# STM32-PROX_6.net
KiCad netlist of a schematic drawn in Altium Designer
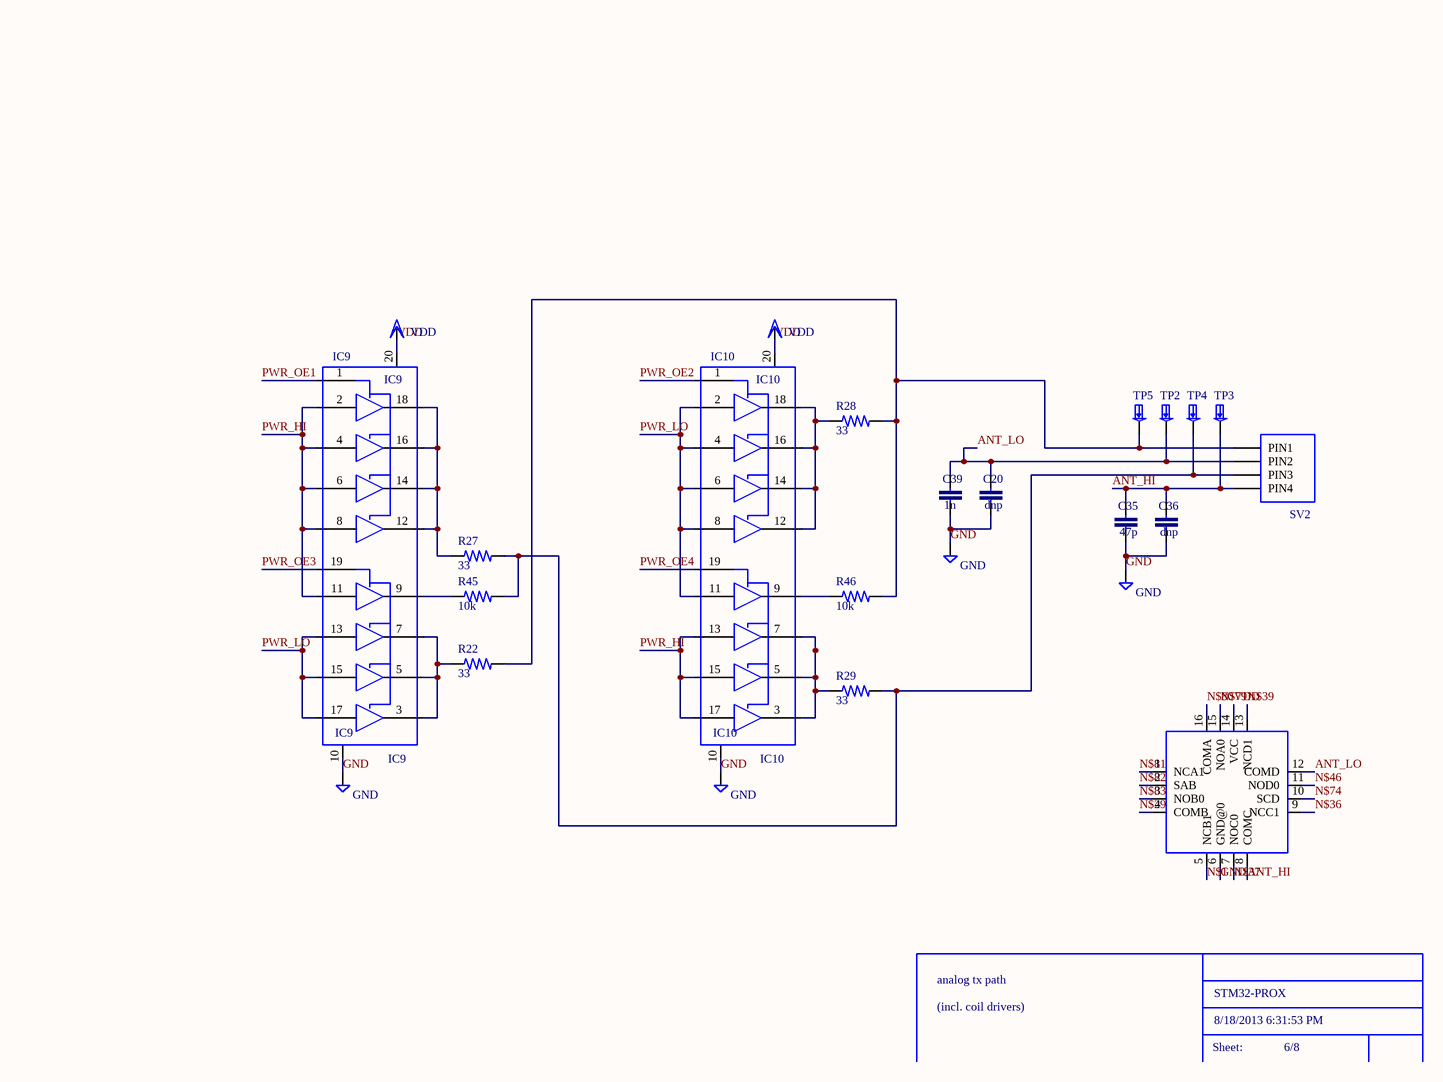
[diagram p0: STM32-PROX_6.SchDoc]

(export (version "E")
  (design (tool "Eeschema 10.0.6"))
  (components
    (comp (ref "C20")
      (value "dnp")
      (footprint "RLC_0603")
      (libsource (lib "STM32-PROX") (part "CAPACITORRLC_0603"))
    )
    (comp (ref "C35")
      (value "47p")
      (footprint "RLC_0603")
      (libsource (lib "STM32-PROX") (part "CAPACITORRLC_0603"))
    )
    (comp (ref "C36")
      (value "dnp")
      (footprint "RLC_0603")
      (libsource (lib "STM32-PROX") (part "CAPACITORRLC_0603"))
    )
    (comp (ref "C39")
      (value "1n")
      (footprint "RLC_0603")
      (libsource (lib "STM32-PROX") (part "CAPACITORRLC_0603"))
    )
    (comp (ref "FRAME5") (value "~") (libsource (lib "STM32-PROX") (part "A4L-LOC")))
    (comp (ref "IC9")
      (value "~")
      (footprint "TSSOP-20")
      (libsource (lib "STM32-PROX") (part "74XX244-OCTAL-TRISTATE-BUFFERS"))
    )
    (comp (ref "IC10")
      (value "~")
      (footprint "TSSOP-20")
      (libsource (lib "STM32-PROX") (part "74XX244-OCTAL-TRISTATE-BUFFERS"))
    )
    (comp (ref "IC12") (value "~") (footprint "QFN16") (libsource (lib "STM32-PROX") (part "NLAST44599")))
    (comp (ref "R22")
      (value "33")
      (footprint "RLC_0603")
      (libsource (lib "STM32-PROX") (part "RESISTORRLC_0603"))
    )
    (comp (ref "R27")
      (value "33")
      (footprint "RLC_0603")
      (libsource (lib "STM32-PROX") (part "RESISTORRLC_0603"))
    )
    (comp (ref "R28")
      (value "33")
      (footprint "RLC_0603")
      (libsource (lib "STM32-PROX") (part "RESISTORRLC_0603"))
    )
    (comp (ref "R29")
      (value "33")
      (footprint "RLC_0603")
      (libsource (lib "STM32-PROX") (part "RESISTORRLC_0603"))
    )
    (comp (ref "R45")
      (value "10k")
      (footprint "RLC_0603")
      (libsource (lib "STM32-PROX") (part "RESISTORRLC_0603"))
    )
    (comp (ref "R46")
      (value "10k")
      (footprint "RLC_0603")
      (libsource (lib "STM32-PROX") (part "RESISTORRLC_0603"))
    )
    (comp (ref "SV2")
      (value "~")
      (footprint "HIROSE-MQ172-4POS")
      (libsource (lib "STM32-PROX") (part "HIROSE-MQ172-4POS"))
    )
    (comp (ref "TP2")
      (value "~")
      (footprint "KEYSTONE-SMD-TESTPOINT-5015")
      (libsource (lib "STM32-PROX") (part "TESTPADKEYSTONE-SMD"))
    )
    (comp (ref "TP3")
      (value "~")
      (footprint "KEYSTONE-SMD-TESTPOINT-5015")
      (libsource (lib "STM32-PROX") (part "TESTPADKEYSTONE-SMD"))
    )
    (comp (ref "TP4")
      (value "~")
      (footprint "KEYSTONE-SMD-TESTPOINT-5015")
      (libsource (lib "STM32-PROX") (part "TESTPADKEYSTONE-SMD"))
    )
    (comp (ref "TP5")
      (value "~")
      (footprint "KEYSTONE-SMD-TESTPOINT-5015")
      (libsource (lib "STM32-PROX") (part "TESTPADKEYSTONE-SMD"))
    )
    (comp (ref "V26") (value "GND") (libsource (lib "STM32-PROX") (part "GND")))
    (comp (ref "V27") (value "GND") (libsource (lib "STM32-PROX") (part "GND")))
    (comp (ref "V41") (value "GND") (libsource (lib "STM32-PROX") (part "GND")))
    (comp (ref "V47") (value "GND") (libsource (lib "STM32-PROX") (part "GND")))
    (comp (ref "VDD5") (value "VDD") (libsource (lib "STM32-PROX") (part "VDD")))
    (comp (ref "VDD6") (value "VDD") (libsource (lib "STM32-PROX") (part "VDD")))
  )
  (nets
    (net (code "1") (name "/ANT_HI") (class "Default")
      (node (ref "C35") (pin "1") (pinfunction "1_1") (pintype "passive"))
      (node (ref "C36") (pin "1") (pinfunction "1_1") (pintype "passive"))
      (node (ref "IC12") (pin "8") (pinfunction "COMC_8") (pintype "passive"))
      (node (ref "SV2") (pin "4") (pinfunction "PIN4_4") (pintype "passive"))
      (node (ref "TP3") (pin "1") (pinfunction "P$1_1") (pintype "passive"))
    )
    (net (code "2") (name "/ANT_LO") (class "Default")
      (node (ref "C20") (pin "1") (pinfunction "1_1") (pintype "passive"))
      (node (ref "C39") (pin "1") (pinfunction "1_1") (pintype "passive"))
      (node (ref "IC12") (pin "12") (pinfunction "COMD_12") (pintype "passive"))
      (node (ref "SV2") (pin "2") (pinfunction "PIN2_2") (pintype "passive"))
      (node (ref "TP2") (pin "1") (pinfunction "P$1_1") (pintype "passive"))
    )
    (net (code "3") (name "/GND") (class "Default")
      (node (ref "C20") (pin "2") (pinfunction "2_2") (pintype "passive"))
      (node (ref "C35") (pin "2") (pinfunction "2_2") (pintype "passive"))
      (node (ref "C36") (pin "2") (pinfunction "2_2") (pintype "passive"))
      (node (ref "C39") (pin "2") (pinfunction "2_2") (pintype "passive"))
      (node (ref "IC10") (pin "10") (pinfunction "VSS_10") (pintype "passive"))
      (node (ref "IC12") (pin "6") (pinfunction "GND@0_6") (pintype "passive"))
      (node (ref "IC9") (pin "10") (pinfunction "VSS_10") (pintype "passive"))
      (node (ref "V26") (pin "0") (pinfunction "GND_0") (pintype "passive"))
      (node (ref "V27") (pin "0") (pinfunction "GND_0") (pintype "passive"))
      (node (ref "V41") (pin "0") (pinfunction "GND_0") (pintype "passive"))
      (node (ref "V47") (pin "0") (pinfunction "GND_0") (pintype "passive"))
    )
    (net (code "4") (name "/N$1") (class "Default")
      (node (ref "IC12") (pin "5") (pinfunction "NCB1_5") (pintype "passive"))
    )
    (net (code "5") (name "/N$29") (class "Default")
      (node (ref "IC12") (pin "4") (pinfunction "COMB_4") (pintype "passive"))
    )
    (net (code "6") (name "/N$36") (class "Default")
      (node (ref "IC12") (pin "9") (pinfunction "NCC1_9") (pintype "passive"))
    )
    (net (code "7") (name "/N$37") (class "Default")
      (node (ref "IC12") (pin "7") (pinfunction "NOC0_7") (pintype "passive"))
    )
    (net (code "8") (name "/N$39") (class "Default")
      (node (ref "IC12") (pin "13") (pinfunction "NCD1_13") (pintype "passive"))
    )
    (net (code "9") (name "/N$46") (class "Default")
      (node (ref "IC12") (pin "11") (pinfunction "NOD0_11") (pintype "passive"))
    )
    (net (code "10") (name "/N$74") (class "Default")
      (node (ref "IC12") (pin "10") (pinfunction "SCD_10") (pintype "passive"))
    )
    (net (code "11") (name "/N$79") (class "Default")
      (node (ref "IC12") (pin "15") (pinfunction "NOA0_15") (pintype "passive"))
    )
    (net (code "12") (name "/N$80") (class "Default")
      (node (ref "IC12") (pin "16") (pinfunction "COMA_16") (pintype "passive"))
    )
    (net (code "13") (name "/N$81") (class "Default")
      (node (ref "IC12") (pin "1") (pinfunction "NCA1_1") (pintype "passive"))
    )
    (net (code "14") (name "/N$82") (class "Default")
      (node (ref "IC12") (pin "2") (pinfunction "SAB_2") (pintype "passive"))
    )
    (net (code "15") (name "/N$83") (class "Default")
      (node (ref "IC12") (pin "3") (pinfunction "NOB0_3") (pintype "passive"))
    )
    (net (code "16") (name "/PWR_HI") (class "Default")
      (node (ref "IC10") (pin "13") (pinfunction "2A2_13") (pintype "passive"))
      (node (ref "IC10") (pin "15") (pinfunction "2A3_15") (pintype "passive"))
      (node (ref "IC10") (pin "17") (pinfunction "2A4_17") (pintype "passive"))
      (node (ref "IC9") (pin "11") (pinfunction "2A1_11") (pintype "passive"))
      (node (ref "IC9") (pin "2") (pinfunction "1A1_2") (pintype "passive"))
      (node (ref "IC9") (pin "4") (pinfunction "1A2_4") (pintype "passive"))
      (node (ref "IC9") (pin "6") (pinfunction "1A3_6") (pintype "passive"))
      (node (ref "IC9") (pin "8") (pinfunction "1A4_8") (pintype "passive"))
    )
    (net (code "17") (name "/PWR_LO") (class "Default")
      (node (ref "IC10") (pin "11") (pinfunction "2A1_11") (pintype "passive"))
      (node (ref "IC10") (pin "2") (pinfunction "1A1_2") (pintype "passive"))
      (node (ref "IC10") (pin "4") (pinfunction "1A2_4") (pintype "passive"))
      (node (ref "IC10") (pin "6") (pinfunction "1A3_6") (pintype "passive"))
      (node (ref "IC10") (pin "8") (pinfunction "1A4_8") (pintype "passive"))
      (node (ref "IC9") (pin "13") (pinfunction "2A2_13") (pintype "passive"))
      (node (ref "IC9") (pin "15") (pinfunction "2A3_15") (pintype "passive"))
      (node (ref "IC9") (pin "17") (pinfunction "2A4_17") (pintype "passive"))
    )
    (net (code "18") (name "/PWR_OE1") (class "Default")
      (node (ref "IC9") (pin "1") (pinfunction "1NOE_1") (pintype "passive"))
    )
    (net (code "19") (name "/PWR_OE2") (class "Default")
      (node (ref "IC10") (pin "1") (pinfunction "1NOE_1") (pintype "passive"))
    )
    (net (code "20") (name "/PWR_OE3") (class "Default")
      (node (ref "IC9") (pin "19") (pinfunction "2NOE_19") (pintype "passive"))
    )
    (net (code "21") (name "/PWR_OE4") (class "Default")
      (node (ref "IC10") (pin "19") (pinfunction "2NOE_19") (pintype "passive"))
    )
    (net (code "22") (name "/VDD") (class "Default")
      (node (ref "IC10") (pin "20") (pinfunction "VDD_20") (pintype "passive"))
      (node (ref "IC12") (pin "14") (pinfunction "VCC_14") (pintype "passive"))
      (node (ref "IC9") (pin "20") (pinfunction "VDD_20") (pintype "passive"))
      (node (ref "VDD5") (pin "0") (pinfunction "VDD_0") (pintype "passive"))
      (node (ref "VDD6") (pin "0") (pinfunction "VDD_0") (pintype "passive"))
    )
    (net (code "23") (name "Net-(IC9-1Y1)") (class "Default")
      (node (ref "IC9") (pin "12") (pinfunction "1Y4_12") (pintype "passive"))
      (node (ref "IC9") (pin "14") (pinfunction "1Y3_14") (pintype "passive"))
      (node (ref "IC9") (pin "16") (pinfunction "1Y2_16") (pintype "passive"))
      (node (ref "IC9") (pin "18") (pinfunction "1Y1_18") (pintype "passive"))
      (node (ref "R27") (pin "1") (pinfunction "1_1") (pintype "passive"))
    )
    (net (code "24") (name "Net-(IC9-2Y1)") (class "Default")
      (node (ref "IC9") (pin "9") (pinfunction "2Y1_9") (pintype "passive"))
      (node (ref "R45") (pin "1") (pinfunction "1_1") (pintype "passive"))
    )
    (net (code "25") (name "Net-(IC9-2Y2)") (class "Default")
      (node (ref "IC9") (pin "3") (pinfunction "2Y4_3") (pintype "passive"))
      (node (ref "IC9") (pin "5") (pinfunction "2Y3_5") (pintype "passive"))
      (node (ref "IC9") (pin "7") (pinfunction "2Y2_7") (pintype "passive"))
      (node (ref "R22") (pin "1") (pinfunction "1_1") (pintype "passive"))
    )
    (net (code "26") (name "Net-(IC10-1Y1)") (class "Default")
      (node (ref "IC10") (pin "12") (pinfunction "1Y4_12") (pintype "passive"))
      (node (ref "IC10") (pin "14") (pinfunction "1Y3_14") (pintype "passive"))
      (node (ref "IC10") (pin "16") (pinfunction "1Y2_16") (pintype "passive"))
      (node (ref "IC10") (pin "18") (pinfunction "1Y1_18") (pintype "passive"))
      (node (ref "R28") (pin "1") (pinfunction "1_1") (pintype "passive"))
    )
    (net (code "27") (name "Net-(IC10-2Y1)") (class "Default")
      (node (ref "IC10") (pin "9") (pinfunction "2Y1_9") (pintype "passive"))
      (node (ref "R46") (pin "1") (pinfunction "1_1") (pintype "passive"))
    )
    (net (code "28") (name "Net-(IC10-2Y2)") (class "Default")
      (node (ref "IC10") (pin "3") (pinfunction "2Y4_3") (pintype "passive"))
      (node (ref "IC10") (pin "5") (pinfunction "2Y3_5") (pintype "passive"))
      (node (ref "IC10") (pin "7") (pinfunction "2Y2_7") (pintype "passive"))
      (node (ref "R29") (pin "1") (pinfunction "1_1") (pintype "passive"))
    )
    (net (code "29") (name "Net-(SV2-PIN1)") (class "Default")
      (node (ref "R22") (pin "2") (pinfunction "2_2") (pintype "passive"))
      (node (ref "R28") (pin "2") (pinfunction "2_2") (pintype "passive"))
      (node (ref "R46") (pin "2") (pinfunction "2_2") (pintype "passive"))
      (node (ref "SV2") (pin "1") (pinfunction "PIN1_1") (pintype "passive"))
      (node (ref "TP5") (pin "1") (pinfunction "P$1_1") (pintype "passive"))
    )
    (net (code "30") (name "Net-(SV2-PIN3)") (class "Default")
      (node (ref "R27") (pin "2") (pinfunction "2_2") (pintype "passive"))
      (node (ref "R29") (pin "2") (pinfunction "2_2") (pintype "passive"))
      (node (ref "R45") (pin "2") (pinfunction "2_2") (pintype "passive"))
      (node (ref "SV2") (pin "3") (pinfunction "PIN3_3") (pintype "passive"))
      (node (ref "TP4") (pin "1") (pinfunction "P$1_1") (pintype "passive"))
    )
  )
)
